# dsa.net
KiCad netlist of a schematic drawn in Altium Designer
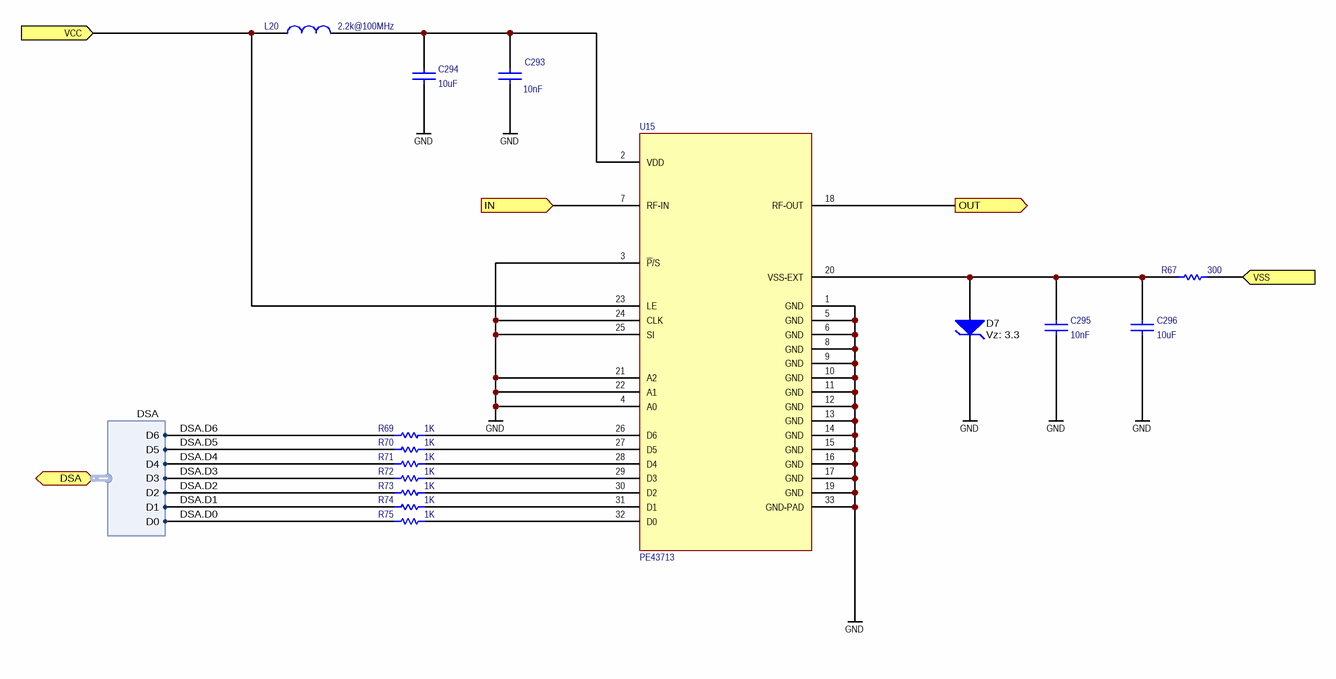
[diagram p0: dsa.SchDoc]

(export (version "E")
  (design (tool "Eeschema 10.0.6"))
  (components
    (comp (ref "C293")
      (value "10nF")
      (footprint "CAPC100X50X55L25N")
      (description "Ceramic Capacitor 10nF ±10% 50V X7R 0402")
      (fields (field (name "VOLTAGE") "50V") (field (name "MANUFACTURER") "Murata"))
      (libsource (lib "Graviton") (part "CAP 0402"))
    )
    (comp (ref "C294")
      (value "10uF")
      (footprint "CAPC160X80X90L20N")
      (description "Ceramic Capacitor 10uF ±20% 25V X5R 0603")
      (fields (field (name "MANUFACTURER") "Murata") (field (name "VOLTAGE") "25V"))
      (libsource (lib "generic") (part "CAP 0603"))
    )
    (comp (ref "C295")
      (value "10nF")
      (footprint "CAPC100X50X55L25N")
      (description "Ceramic Capacitor 10nF ±10% 50V X7R 0402")
      (fields (field (name "VOLTAGE") "50V") (field (name "MANUFACTURER") "Murata"))
      (libsource (lib "Graviton") (part "CAP 0402"))
    )
    (comp (ref "C296")
      (value "10uF")
      (footprint "CAPC160X80X90L20N")
      (description "Ceramic Capacitor 10uF ±20% 25V X5R 0603")
      (fields (field (name "MANUFACTURER") "Murata") (field (name "VOLTAGE") "25V"))
      (libsource (lib "generic") (part "CAP 0603"))
    )
    (comp (ref "D7")
      (value "BZT585B3V3T-7")
      (footprint "generic:SOD523")
      (description "3.3V Zener Diode SOD-523")
      (fields (field (name "MANUFACTURER") "Diodes Inc") (field (name "VZ") "3.3"))
      (libsource (lib "generic") (part "ZENER"))
    )
    (comp (ref "L20")
      (value "2.2k@100MHz")
      (footprint "INDC1005X55N")
      (description "Ferrite Bead 2.2k@100MHz 150mA 0402")
      (fields (field (name "MANUFACTURER") "TDK") (field (name "Comment") "MMZ1005A222ET000"))
      (libsource (lib "*") (part "INDUCTANCE1"))
    )
    (comp (ref "R67")
      (value "300")
      (footprint "RESC2012X70N")
      (description "Thin Film Resistor 300 +/-0.1% SMD 0805")
      (fields (field (name "TOLERANCE") "±0.1%") (field (name "MANUFACTURER") "Susumu"))
      (libsource (lib "generic") (part "RES"))
    )
    (comp (ref "R69")
      (value "1K")
      (footprint "RESC1005X40N")
      (description "Thick Film Resistor 1k ±1% 0402")
      (fields (field (name "MANUFACTURER") "Yageo") (field (name "TOLERANCE") "±1%"))
      (libsource (lib "Graviton") (part "RES 0402"))
    )
    (comp (ref "R70")
      (value "1K")
      (footprint "RESC1005X40N")
      (description "Thick Film Resistor 1k ±1% 0402")
      (fields (field (name "MANUFACTURER") "Yageo") (field (name "TOLERANCE") "±1%"))
      (libsource (lib "Graviton") (part "RES 0402"))
    )
    (comp (ref "R71")
      (value "1K")
      (footprint "RESC1005X40N")
      (description "Thick Film Resistor 1k ±1% 0402")
      (fields (field (name "MANUFACTURER") "Yageo") (field (name "TOLERANCE") "±1%"))
      (libsource (lib "Graviton") (part "RES 0402"))
    )
    (comp (ref "R72")
      (value "1K")
      (footprint "RESC1005X40N")
      (description "Thick Film Resistor 1k ±1% 0402")
      (fields (field (name "MANUFACTURER") "Yageo") (field (name "TOLERANCE") "±1%"))
      (libsource (lib "Graviton") (part "RES 0402"))
    )
    (comp (ref "R73")
      (value "1K")
      (footprint "RESC1005X40N")
      (description "Thick Film Resistor 1k ±1% 0402")
      (fields (field (name "MANUFACTURER") "Yageo") (field (name "TOLERANCE") "±1%"))
      (libsource (lib "Graviton") (part "RES 0402"))
    )
    (comp (ref "R74")
      (value "1K")
      (footprint "RESC1005X40N")
      (description "Thick Film Resistor 1k ±1% 0402")
      (fields (field (name "MANUFACTURER") "Yageo") (field (name "TOLERANCE") "±1%"))
      (libsource (lib "Graviton") (part "RES 0402"))
    )
    (comp (ref "R75")
      (value "1K")
      (footprint "RESC1005X40N")
      (description "Thick Film Resistor 1k ±1% 0402")
      (fields (field (name "MANUFACTURER") "Yageo") (field (name "TOLERANCE") "±1%"))
      (libsource (lib "Graviton") (part "RES 0402"))
    )
    (comp (ref "U15")
      (value "PE43713")
      (footprint "QFN-PE-32")
      (description "Digital Step Attenuaator, 9kHz-6GHz")
      (fields (field (name "MANUFACTURER") "Peregrine Semiconductor"))
      (libsource (lib "peregrine") (part "PE43713"))
    )
  )
  (nets
    (net (code "2") (name "/DSA.D0") (class "Default")
      (node (ref "R75") (pin "2") (pinfunction "2_2") (pintype "passive"))
    )
    (net (code "3") (name "/DSA.D1") (class "Default")
      (node (ref "R74") (pin "2") (pinfunction "2_2") (pintype "passive"))
    )
    (net (code "4") (name "/DSA.D2") (class "Default")
      (node (ref "R73") (pin "2") (pinfunction "2_2") (pintype "passive"))
    )
    (net (code "5") (name "/DSA.D3") (class "Default")
      (node (ref "R72") (pin "2") (pinfunction "2_2") (pintype "passive"))
    )
    (net (code "6") (name "/DSA.D4") (class "Default")
      (node (ref "R71") (pin "2") (pinfunction "2_2") (pintype "passive"))
    )
    (net (code "7") (name "/DSA.D5") (class "Default")
      (node (ref "R70") (pin "2") (pinfunction "2_2") (pintype "passive"))
    )
    (net (code "8") (name "/DSA.D6") (class "Default")
      (node (ref "R69") (pin "2") (pinfunction "2_2") (pintype "passive"))
    )
    (net (code "9") (name "/IN") (class "Default")
      (node (ref "U15") (pin "7") (pinfunction "RF-IN_7") (pintype "passive"))
    )
    (net (code "10") (name "/OUT") (class "Default")
      (node (ref "U15") (pin "18") (pinfunction "RF-OUT_18") (pintype "passive"))
    )
    (net (code "11") (name "/VCC") (class "Default")
      (node (ref "L20") (pin "1") (pinfunction "1_1") (pintype "passive"))
      (node (ref "U15") (pin "23") (pinfunction "LE_23") (pintype "passive"))
    )
    (net (code "12") (name "/VSS") (class "Default")
      (node (ref "R67") (pin "2") (pinfunction "2_2") (pintype "passive"))
    )
    (net (code "14") (name "GND") (class "Default")
      (node (ref "C293") (pin "1") (pinfunction "1_1") (pintype "passive"))
      (node (ref "C294") (pin "1") (pinfunction "1_1") (pintype "passive"))
      (node (ref "C295") (pin "1") (pinfunction "1_1") (pintype "passive"))
      (node (ref "C296") (pin "1") (pinfunction "1_1") (pintype "passive"))
      (node (ref "D7") (pin "1") (pinfunction "K_1") (pintype "passive"))
      (node (ref "U15") (pin "1") (pinfunction "GND_1") (pintype "passive"))
      (node (ref "U15") (pin "10") (pinfunction "GND_10") (pintype "passive"))
      (node (ref "U15") (pin "11") (pinfunction "GND_11") (pintype "passive"))
      (node (ref "U15") (pin "12") (pinfunction "GND_12") (pintype "passive"))
      (node (ref "U15") (pin "13") (pinfunction "GND_13") (pintype "passive"))
      (node (ref "U15") (pin "14") (pinfunction "GND_14") (pintype "passive"))
      (node (ref "U15") (pin "15") (pinfunction "GND_15") (pintype "passive"))
      (node (ref "U15") (pin "16") (pinfunction "GND_16") (pintype "passive"))
      (node (ref "U15") (pin "17") (pinfunction "GND_17") (pintype "passive"))
      (node (ref "U15") (pin "19") (pinfunction "GND_19") (pintype "passive"))
      (node (ref "U15") (pin "21") (pinfunction "A2_21") (pintype "passive"))
      (node (ref "U15") (pin "22") (pinfunction "A1_22") (pintype "passive"))
      (node (ref "U15") (pin "24") (pinfunction "CLK_24") (pintype "passive"))
      (node (ref "U15") (pin "25") (pinfunction "SI_25") (pintype "passive"))
      (node (ref "U15") (pin "3") (pinfunction "~{P}/S_3") (pintype "passive"))
      (node (ref "U15") (pin "33") (pinfunction "GND-PAD_33") (pintype "passive"))
      (node (ref "U15") (pin "4") (pinfunction "A0_4") (pintype "passive"))
      (node (ref "U15") (pin "5") (pinfunction "GND_5") (pintype "passive"))
      (node (ref "U15") (pin "6") (pinfunction "GND_6") (pintype "passive"))
      (node (ref "U15") (pin "8") (pinfunction "GND_8") (pintype "passive"))
      (node (ref "U15") (pin "9") (pinfunction "GND_9") (pintype "passive"))
    )
    (net (code "15") (name "Net-(D7-A)") (class "Default")
      (node (ref "C295") (pin "2") (pinfunction "2_2") (pintype "passive"))
      (node (ref "C296") (pin "2") (pinfunction "2_2") (pintype "passive"))
      (node (ref "D7") (pin "2") (pinfunction "A_2") (pintype "power_in"))
      (node (ref "R67") (pin "1") (pinfunction "1_1") (pintype "passive"))
      (node (ref "U15") (pin "20") (pinfunction "VSS-EXT_20") (pintype "passive"))
    )
    (net (code "16") (name "Net-(U15-D0)") (class "Default")
      (node (ref "R75") (pin "1") (pinfunction "1_1") (pintype "passive"))
      (node (ref "U15") (pin "32") (pinfunction "D0_32") (pintype "passive"))
    )
    (net (code "17") (name "Net-(U15-D1)") (class "Default")
      (node (ref "R74") (pin "1") (pinfunction "1_1") (pintype "passive"))
      (node (ref "U15") (pin "31") (pinfunction "D1_31") (pintype "passive"))
    )
    (net (code "18") (name "Net-(U15-D2)") (class "Default")
      (node (ref "R73") (pin "1") (pinfunction "1_1") (pintype "passive"))
      (node (ref "U15") (pin "30") (pinfunction "D2_30") (pintype "passive"))
    )
    (net (code "19") (name "Net-(U15-D3)") (class "Default")
      (node (ref "R72") (pin "1") (pinfunction "1_1") (pintype "passive"))
      (node (ref "U15") (pin "29") (pinfunction "D3_29") (pintype "passive"))
    )
    (net (code "20") (name "Net-(U15-D4)") (class "Default")
      (node (ref "R71") (pin "1") (pinfunction "1_1") (pintype "passive"))
      (node (ref "U15") (pin "28") (pinfunction "D4_28") (pintype "passive"))
    )
    (net (code "21") (name "Net-(U15-D5)") (class "Default")
      (node (ref "R70") (pin "1") (pinfunction "1_1") (pintype "passive"))
      (node (ref "U15") (pin "27") (pinfunction "D5_27") (pintype "passive"))
    )
    (net (code "22") (name "Net-(U15-D6)") (class "Default")
      (node (ref "R69") (pin "1") (pinfunction "1_1") (pintype "passive"))
      (node (ref "U15") (pin "26") (pinfunction "D6_26") (pintype "passive"))
    )
    (net (code "23") (name "Net-(U15-VDD)") (class "Default")
      (node (ref "C293") (pin "2") (pinfunction "2_2") (pintype "passive"))
      (node (ref "C294") (pin "2") (pinfunction "2_2") (pintype "passive"))
      (node (ref "L20") (pin "2") (pinfunction "2_2") (pintype "passive"))
      (node (ref "U15") (pin "2") (pinfunction "VDD_2") (pintype "passive"))
    )
  )
)
